# RiskChemi_Monitor_V1_05M1.net
KiCad netlist of a schematic drawn in Altium Designer
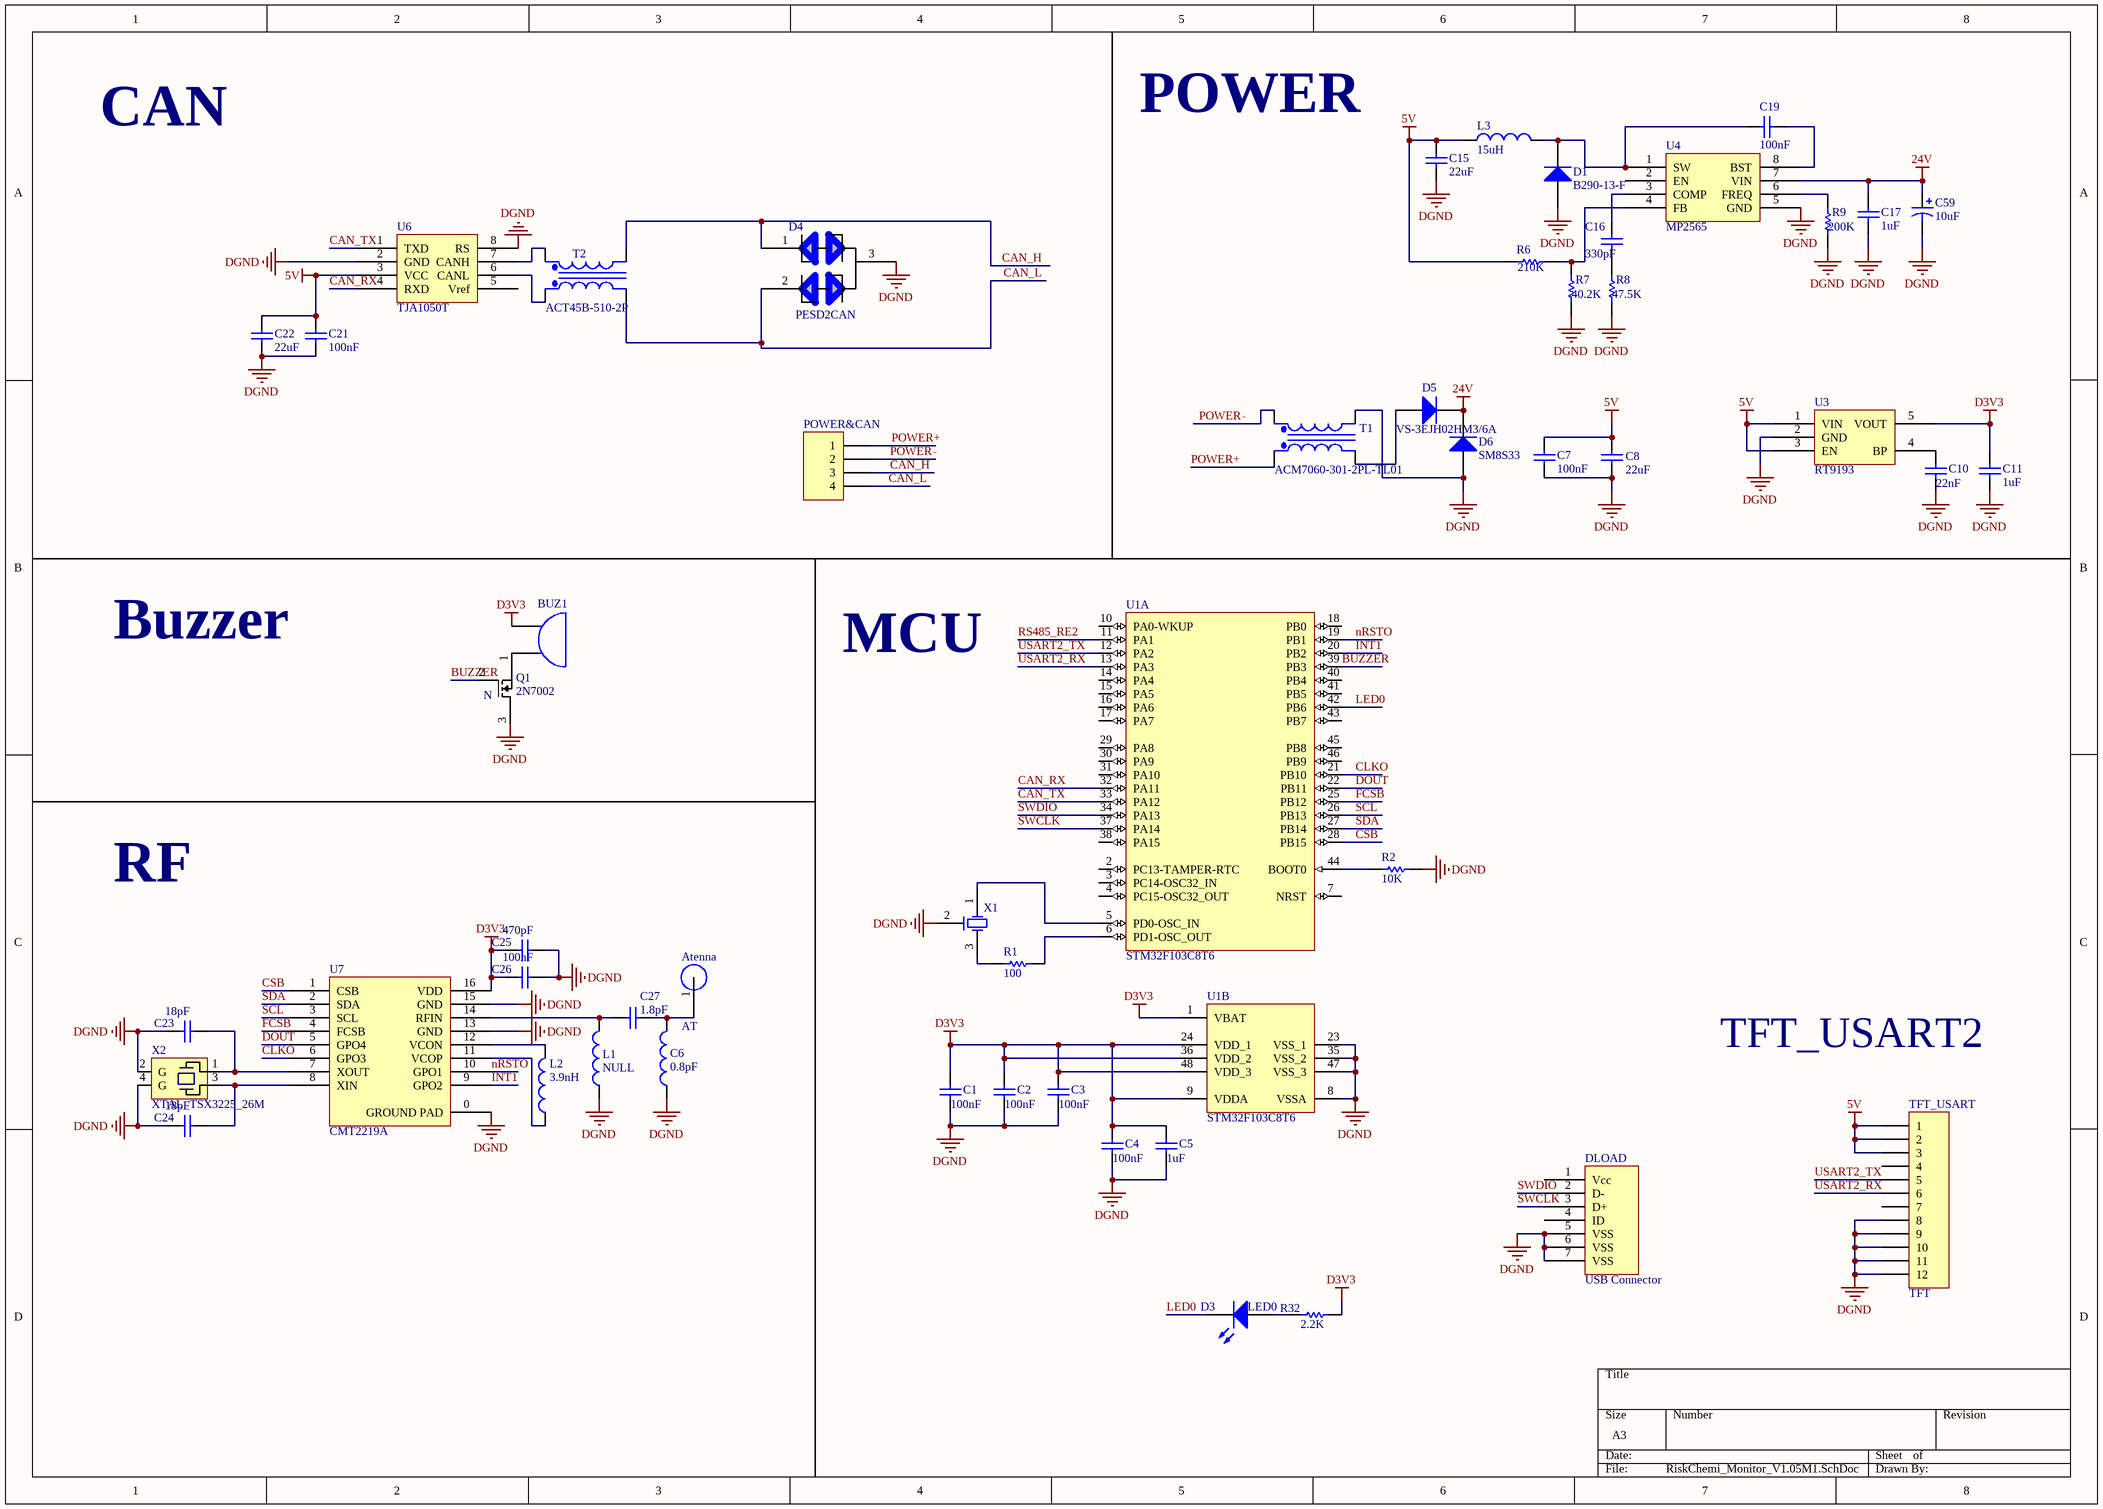
[diagram p0: RiskChemi_Monitor_V1.05M1.SchDoc]

(export (version "E")
  (design (tool "Eeschema 10.0.6"))
  (components
    (comp (ref "Atenna") (value "AT") (footprint "433MHz Atenna") (libsource (lib "MySchlib1") (part "AT")))
    (comp (ref "BUZ1")
      (value "BUZZER")
      (footprint "BUZ0905")
      (description "Buzzer")
      (libsource (lib "杂元件库") (part "BUZZER"))
    )
    (comp (ref "C1")
      (value "100nF")
      (footprint "0603")
      (description "Capacitor")
      (fields (field (name "PUBLISHER") "Altium Limited"))
      (libsource (lib "Miscellaneous Devices") (part "Cap"))
    )
    (comp (ref "C2")
      (value "100nF")
      (footprint "0603")
      (description "Capacitor")
      (fields (field (name "PUBLISHER") "Altium Limited"))
      (libsource (lib "Miscellaneous Devices") (part "Cap"))
    )
    (comp (ref "C3")
      (value "100nF")
      (footprint "0603")
      (description "Capacitor")
      (fields (field (name "PUBLISHER") "Altium Limited"))
      (libsource (lib "Miscellaneous Devices") (part "Cap"))
    )
    (comp (ref "C4")
      (value "100nF")
      (footprint "0603")
      (description "Capacitor")
      (fields (field (name "PUBLISHER") "Altium Limited"))
      (libsource (lib "Miscellaneous Devices") (part "Cap"))
    )
    (comp (ref "C5")
      (value "1uF")
      (footprint "0603")
      (description "Capacitor")
      (fields (field (name "PUBLISHER") "Altium Limited"))
      (libsource (lib "Miscellaneous Devices") (part "Cap"))
    )
    (comp (ref "C6")
      (value "0.8pF")
      (footprint "Miscellaneous Devices:0402")
      (description "Inductor")
      (fields (field (name "PUBLISHER") "Altium Limited"))
      (libsource (lib "Miscellaneous Devices") (part "Inductor"))
    )
    (comp (ref "C7")
      (value "100nF")
      (footprint "0805")
      (description "Capacitor,100V")
      (fields (field (name "PUBLISHER") "Altium Limited"))
      (libsource (lib "Miscellaneous Devices") (part "Cap"))
    )
    (comp (ref "C8")
      (value "22uF")
      (footprint "0805")
      (description "Capacitor")
      (fields (field (name "PUBLISHER") "Altium Limited"))
      (libsource (lib "Miscellaneous Devices") (part "Cap"))
    )
    (comp (ref "C10")
      (value "22nF")
      (footprint "BinFeng:0603")
      (description "Capacitor")
      (fields (field (name "PUBLISHER") "Altium Limited"))
      (libsource (lib "Miscellaneous Devices") (part "Cap"))
    )
    (comp (ref "C11")
      (value "1uF")
      (footprint "BinFeng:0603")
      (description "Capacitor")
      (fields (field (name "PUBLISHER") "Altium Limited"))
      (libsource (lib "Miscellaneous Devices") (part "Cap"))
    )
    (comp (ref "C15")
      (value "22uF")
      (footprint "0805")
      (description "Capacitor,50V")
      (fields (field (name "PUBLISHER") "Altium Limited"))
      (libsource (lib "Miscellaneous Devices") (part "Cap"))
    )
    (comp (ref "C16")
      (value "330pF")
      (footprint "BinFeng:0402")
      (description "Capacitor")
      (fields (field (name "PUBLISHER") "Altium Limited"))
      (libsource (lib "Miscellaneous Devices") (part "Cap"))
    )
    (comp (ref "C17")
      (value "1uF")
      (footprint "0805")
      (description "Capacitor,100V")
      (fields (field (name "PUBLISHER") "Altium Limited"))
      (libsource (lib "Miscellaneous Devices") (part "Cap"))
    )
    (comp (ref "C19")
      (value "100nF")
      (footprint "BinFeng:0402")
      (description "Capacitor")
      (fields (field (name "PUBLISHER") "Altium Limited"))
      (libsource (lib "Miscellaneous Devices") (part "Cap"))
    )
    (comp (ref "C21")
      (value "100nF")
      (footprint "0603")
      (description "Capacitor")
      (fields (field (name "PUBLISHER") "Altium Limited"))
      (libsource (lib "Miscellaneous Devices") (part "Cap"))
    )
    (comp (ref "C22")
      (value "22uF")
      (footprint "0805")
      (description "Capacitor")
      (fields (field (name "PUBLISHER") "Altium Limited"))
      (libsource (lib "Miscellaneous Devices") (part "Cap"))
    )
    (comp (ref "C23")
      (value "18pF")
      (footprint "BinFeng:0402")
      (description "Capacitor")
      (fields (field (name "PUBLISHER") "Altium Limited"))
      (libsource (lib "Miscellaneous Devices") (part "Cap"))
    )
    (comp (ref "C24")
      (value "18pF")
      (footprint "BinFeng:0402")
      (description "Capacitor")
      (fields (field (name "PUBLISHER") "Altium Limited"))
      (libsource (lib "Miscellaneous Devices") (part "Cap"))
    )
    (comp (ref "C25")
      (value "470pF")
      (footprint "BinFeng:0402")
      (description "Capacitor")
      (fields (field (name "PUBLISHER") "Altium Limited"))
      (libsource (lib "Miscellaneous Devices") (part "Cap"))
    )
    (comp (ref "C26")
      (value "100nF")
      (footprint "BinFeng:0603")
      (description "Capacitor")
      (fields (field (name "PUBLISHER") "Altium Limited"))
      (libsource (lib "Miscellaneous Devices") (part "Cap"))
    )
    (comp (ref "C27")
      (value "1.8pF")
      (footprint "BinFeng:nosilk_0402")
      (description "Capacitor")
      (fields (field (name "PUBLISHER") "Altium Limited"))
      (libsource (lib "Miscellaneous Devices") (part "Cap"))
    )
    (comp (ref "C59")
      (value "10uF")
      (footprint "6032_pol")
      (description "Polarized Capacitor (Radial)")
      (fields (field (name "PUBLISHER") "Altium Limited"))
      (libsource (lib "Miscellaneous Devices") (part "Cap Pol1"))
    )
    (comp (ref "D1")
      (value "B290-13-F")
      (footprint "back:B290")
      (description "Default Diode")
      (fields (field (name "PUBLISHER") "Altium Limited"))
      (libsource (lib "Miscellaneous Devices") (part "Diode"))
    )
    (comp (ref "D3")
      (value "LED0")
      (footprint "LED")
      (description "green LED")
      (fields (field (name "PUBLISHER") "Altium Limited"))
      (libsource (lib "Miscellaneous Devices") (part "LED0"))
    )
    (comp (ref "D4")
      (value "PESD2CAN")
      (footprint "SOT23")
      (libsource (lib "BinFeng_Connectors") (part "PESD1CAN"))
    )
    (comp (ref "D5")
      (value "VS-3EJH02HM3/6A")
      (footprint "back:B290")
      (description "1 Amp General Purpose Rectifier")
      (fields (field (name "PUBLISHER") "Altium Limited"))
      (libsource (lib "Miscellaneous Devices") (part "Diode 1N4007"))
    )
    (comp (ref "D6")
      (value "SM8S33")
      (footprint "SM8S")
      (description "1 Amp General Purpose Rectifier")
      (fields (field (name "PUBLISHER") "Altium Limited"))
      (libsource (lib "Miscellaneous Devices") (part "Diode 1N4007"))
    )
    (comp (ref "DLOAD")
      (value "USB Connector")
      (footprint "Mini_USB")
      (libsource (lib "BinFeng_Connectors") (part "Component_1"))
    )
    (comp (ref "L1")
      (value "NULL")
      (footprint "Miscellaneous Devices:0402")
      (description "Inductor")
      (fields (field (name "PUBLISHER") "Altium Limited"))
      (libsource (lib "Miscellaneous Devices") (part "Inductor"))
    )
    (comp (ref "L2")
      (value "3.9nH")
      (footprint "BinFeng:0603")
      (description "Inductor")
      (fields (field (name "PUBLISHER") "Altium Limited"))
      (libsource (lib "Miscellaneous Devices") (part "Inductor"))
    )
    (comp (ref "L3")
      (value "15uH")
      (footprint "4*4 Inductor")
      (description "Inductor, 1A")
      (fields (field (name "PUBLISHER") "Altium Limited"))
      (libsource (lib "Miscellaneous Devices") (part "Inductor"))
    )
    (comp (ref "POWER&CAN")
      (value "Header 4")
      (footprint "4_CLK_HEADER")
      (description "Header, 4-Pin")
      (fields (field (name "PUBLISHER") "Altium Limited"))
      (libsource (lib "Miscellaneous Connectors") (part "Header 4"))
    )
    (comp (ref "Q1") (value "2N7002") (footprint "2N7002") (libsource (lib "seeder") (part "N-MOSFET")))
    (comp (ref "R1")
      (value "100")
      (footprint "back:0603")
      (description "Resistor")
      (fields (field (name "PUBLISHER") "Altium Limited"))
      (libsource (lib "Miscellaneous Devices") (part "Res1"))
    )
    (comp (ref "R2")
      (value "10K")
      (footprint "back:0603")
      (description "Resistor")
      (fields (field (name "PUBLISHER") "Altium Limited"))
      (libsource (lib "Miscellaneous Devices") (part "Res1"))
    )
    (comp (ref "R6")
      (value "210K")
      (footprint "BinFeng:0402")
      (description "Resistor")
      (fields (field (name "PUBLISHER") "Altium Limited"))
      (libsource (lib "Miscellaneous Devices") (part "Res1"))
    )
    (comp (ref "R7")
      (value "40.2K")
      (footprint "BinFeng:0402")
      (description "Resistor")
      (fields (field (name "PUBLISHER") "Altium Limited"))
      (libsource (lib "Miscellaneous Devices") (part "Res1"))
    )
    (comp (ref "R8")
      (value "47.5K")
      (footprint "BinFeng:0402")
      (description "Resistor")
      (fields (field (name "PUBLISHER") "Altium Limited"))
      (libsource (lib "Miscellaneous Devices") (part "Res1"))
    )
    (comp (ref "R9")
      (value "200K")
      (footprint "BinFeng:0402")
      (description "Resistor")
      (fields (field (name "PUBLISHER") "Altium Limited"))
      (libsource (lib "Miscellaneous Devices") (part "Res1"))
    )
    (comp (ref "R32")
      (value "2.2K")
      (footprint "BinFeng:0603")
      (description "Resistor")
      (fields (field (name "PUBLISHER") "Altium Limited"))
      (libsource (lib "Miscellaneous Devices") (part "Res1"))
    )
    (comp (ref "T1")
      (value "ACM7060-301-2PL-TL01")
      (footprint "ACM7060-301-2P-TL01")
      (description "Transformer (Equivalent Circuit Model)")
      (fields (field (name "PUBLISHER") "Altium Limited"))
      (libsource (lib "Miscellaneous Devices") (part "Trans Eq"))
    )
    (comp (ref "T2")
      (value "ACT45B-510-2P")
      (footprint "ACT45B-510-2P")
      (description "Transformer (Equivalent Circuit Model)")
      (fields (field (name "PUBLISHER") "Altium Limited"))
      (libsource (lib "Miscellaneous Devices") (part "Trans Eq"))
    )
    (comp (ref "TFT_USART")
      (value "TFT")
      (footprint "FCC_10pin_1mm")
      (description "Header, 12-Pin")
      (fields (field (name "PUBLISHER") "Altium Limited"))
      (libsource (lib "Miscellaneous Connectors") (part "Header 12"))
    )
    (comp (ref "U1")
      (value "STM32F103C8T6")
      (footprint "STM-LQFP48_N")
      (libsource (lib "STMicroelectronics STM32 F1") (part "STM32F103C8T6"))
    )
    (comp (ref "U3") (value "RT9193") (footprint "SOT-23-5") (libsource (lib "BinFeng_IC") (part "RT9193")))
    (comp (ref "U4")
      (value "MP2565")
      (footprint "SO8")
      (description "DCDC 4.5V~28V input 1.8V ~5V output low power")
      (libsource (lib "BinFeng_IC") (part "MP1584"))
    )
    (comp (ref "U6")
      (value "TJA1050T")
      (footprint "SO8")
      (description "CAN Tranceiver")
      (libsource (lib "BinFeng_IC") (part "TJA1050T"))
    )
    (comp (ref "U7")
      (value "CMT2219A")
      (footprint "back:QFN16")
      (libsource (lib "BinFeng_IC") (part "CMT2219A"))
    )
    (comp (ref "X1") (value "8M smd") (footprint "8Mhz_XTAL") (libsource (lib "Schlib1") (part "8M smd")))
    (comp (ref "X2")
      (value "XTAL_TSX3225_26M")
      (footprint "XTAL3225")
      (libsource (lib "BinFeng_IC") (part "XTAL_Negative"))
    )
  )
  (nets
    (net (code "1") (name "/BUZZER") (class "Default")
      (node (ref "Q1") (pin "2") (pinfunction "G_2") (pintype "passive"))
      (node (ref "U1") (pin "39") (pinfunction "PB3_39") (pintype "bidirectional"))
    )
    (net (code "2") (name "/CAN_H") (class "Default")
      (node (ref "D4") (pin "1") (pinfunction "11_1") (pintype "passive"))
      (node (ref "POWER&CAN") (pin "3") (pinfunction "3_3") (pintype "passive"))
      (node (ref "T2") (pin "4") (pinfunction "Sec-_4") (pintype "passive"))
    )
    (net (code "3") (name "/CAN_L") (class "Default")
      (node (ref "D4") (pin "2") (pinfunction "12_2") (pintype "passive"))
      (node (ref "POWER&CAN") (pin "4") (pinfunction "4_4") (pintype "passive"))
      (node (ref "T2") (pin "2") (pinfunction "Pri-_2") (pintype "passive"))
    )
    (net (code "4") (name "/CAN_RX") (class "Default")
      (node (ref "U1") (pin "32") (pinfunction "PA11_32") (pintype "bidirectional"))
      (node (ref "U6") (pin "4") (pinfunction "RXD_4") (pintype "passive"))
    )
    (net (code "5") (name "/CAN_TX") (class "Default")
      (node (ref "U1") (pin "33") (pinfunction "PA12_33") (pintype "bidirectional"))
      (node (ref "U6") (pin "1") (pinfunction "TXD_1") (pintype "passive"))
    )
    (net (code "6") (name "/CLKO") (class "Default")
      (node (ref "U1") (pin "21") (pinfunction "PB10_21") (pintype "bidirectional"))
      (node (ref "U7") (pin "6") (pinfunction "GPO3_6") (pintype "passive"))
    )
    (net (code "7") (name "/CSB") (class "Default")
      (node (ref "U1") (pin "28") (pinfunction "PB15_28") (pintype "bidirectional"))
      (node (ref "U7") (pin "1") (pinfunction "CSB_1") (pintype "passive"))
    )
    (net (code "8") (name "/DOUT") (class "Default")
      (node (ref "U1") (pin "22") (pinfunction "PB11_22") (pintype "bidirectional"))
      (node (ref "U7") (pin "5") (pinfunction "GPO4_5") (pintype "passive"))
    )
    (net (code "9") (name "/FCSB") (class "Default")
      (node (ref "U1") (pin "25") (pinfunction "PB12_25") (pintype "bidirectional"))
      (node (ref "U7") (pin "4") (pinfunction "FCSB_4") (pintype "passive"))
    )
    (net (code "10") (name "/INT1") (class "Default")
      (node (ref "U1") (pin "20") (pinfunction "PB2_20") (pintype "bidirectional"))
      (node (ref "U7") (pin "9") (pinfunction "GPO2_9") (pintype "passive"))
    )
    (net (code "11") (name "/LED0") (class "Default")
      (node (ref "D3") (pin "2") (pinfunction "K_2") (pintype "passive"))
      (node (ref "U1") (pin "42") (pinfunction "PB6_42") (pintype "bidirectional"))
    )
    (net (code "12") (name "/POWER+") (class "Default")
      (node (ref "POWER&CAN") (pin "1") (pinfunction "1_1") (pintype "passive"))
      (node (ref "T1") (pin "1") (pinfunction "Pri+_1") (pintype "passive"))
    )
    (net (code "13") (name "/POWER﹣") (class "Default")
      (node (ref "POWER&CAN") (pin "2") (pinfunction "2_2") (pintype "passive"))
      (node (ref "T1") (pin "3") (pinfunction "Sec+_3") (pintype "passive"))
    )
    (net (code "14") (name "/RS485_RE2") (class "Default")
      (node (ref "U1") (pin "11") (pinfunction "PA1_11") (pintype "bidirectional"))
    )
    (net (code "15") (name "/SCL") (class "Default")
      (node (ref "U1") (pin "26") (pinfunction "PB13_26") (pintype "bidirectional"))
      (node (ref "U7") (pin "3") (pinfunction "SCL_3") (pintype "passive"))
    )
    (net (code "16") (name "/SDA") (class "Default")
      (node (ref "U1") (pin "27") (pinfunction "PB14_27") (pintype "bidirectional"))
      (node (ref "U7") (pin "2") (pinfunction "SDA_2") (pintype "passive"))
    )
    (net (code "17") (name "/SWCLK") (class "Default")
      (node (ref "DLOAD") (pin "3") (pinfunction "D+_3") (pintype "passive"))
      (node (ref "U1") (pin "37") (pinfunction "PA14_37") (pintype "bidirectional"))
    )
    (net (code "18") (name "/SWDIO") (class "Default")
      (node (ref "DLOAD") (pin "2") (pinfunction "D-_2") (pintype "passive"))
      (node (ref "U1") (pin "34") (pinfunction "PA13_34") (pintype "bidirectional"))
    )
    (net (code "19") (name "/USART2_RX") (class "Default")
      (node (ref "TFT_USART") (pin "6") (pinfunction "6_6") (pintype "passive"))
      (node (ref "U1") (pin "13") (pinfunction "PA3_13") (pintype "bidirectional"))
    )
    (net (code "20") (name "/USART2_TX") (class "Default")
      (node (ref "TFT_USART") (pin "5") (pinfunction "5_5") (pintype "passive"))
      (node (ref "U1") (pin "12") (pinfunction "PA2_12") (pintype "bidirectional"))
    )
    (net (code "21") (name "/nRSTO") (class "Default")
      (node (ref "U1") (pin "19") (pinfunction "PB1_19") (pintype "bidirectional"))
      (node (ref "U7") (pin "10") (pinfunction "GPO1_10") (pintype "passive"))
    )
    (net (code "22") (name "5V") (class "Default")
      (node (ref "C15") (pin "2") (pinfunction "2_2") (pintype "passive"))
      (node (ref "C21") (pin "1") (pinfunction "1_1") (pintype "passive"))
      (node (ref "C22") (pin "2") (pinfunction "2_2") (pintype "passive"))
      (node (ref "C7") (pin "2") (pinfunction "2_2") (pintype "passive"))
      (node (ref "C8") (pin "2") (pinfunction "2_2") (pintype "passive"))
      (node (ref "L3") (pin "1") (pinfunction "1_1") (pintype "passive"))
      (node (ref "R6") (pin "2") (pinfunction "2_2") (pintype "passive"))
      (node (ref "TFT_USART") (pin "1") (pinfunction "1_1") (pintype "passive"))
      (node (ref "TFT_USART") (pin "2") (pinfunction "2_2") (pintype "passive"))
      (node (ref "TFT_USART") (pin "3") (pinfunction "3_3") (pintype "passive"))
      (node (ref "U3") (pin "1") (pinfunction "VIN_1") (pintype "passive"))
      (node (ref "U3") (pin "3") (pinfunction "EN_3") (pintype "passive"))
      (node (ref "U6") (pin "3") (pinfunction "VCC_3") (pintype "passive"))
    )
    (net (code "23") (name "24V") (class "Default")
      (node (ref "C17") (pin "2") (pinfunction "2_2") (pintype "passive"))
      (node (ref "C59") (pin "1") (pinfunction "1_1") (pintype "passive"))
      (node (ref "D5") (pin "2") (pinfunction "K_2") (pintype "passive"))
      (node (ref "D6") (pin "2") (pinfunction "K_2") (pintype "passive"))
      (node (ref "U4") (pin "7") (pinfunction "VIN_7") (pintype "passive"))
    )
    (net (code "24") (name "D3V3") (class "Default")
      (node (ref "BUZ1") (pin "1") (pinfunction "A_1") (pintype "passive"))
      (node (ref "C1") (pin "2") (pinfunction "2_2") (pintype "passive"))
      (node (ref "C11") (pin "2") (pinfunction "2_2") (pintype "passive"))
      (node (ref "C2") (pin "2") (pinfunction "2_2") (pintype "passive"))
      (node (ref "C25") (pin "2") (pinfunction "2_2") (pintype "passive"))
      (node (ref "C26") (pin "2") (pinfunction "2_2") (pintype "passive"))
      (node (ref "C3") (pin "2") (pinfunction "2_2") (pintype "passive"))
      (node (ref "C4") (pin "2") (pinfunction "2_2") (pintype "passive"))
      (node (ref "C5") (pin "2") (pinfunction "2_2") (pintype "passive"))
      (node (ref "R32") (pin "1") (pinfunction "1_1") (pintype "passive"))
      (node (ref "U1") (pin "1") (pinfunction "VBAT_1") (pintype "power_in"))
      (node (ref "U1") (pin "24") (pinfunction "VDD_1_24") (pintype "power_in"))
      (node (ref "U1") (pin "36") (pinfunction "VDD_2_36") (pintype "power_in"))
      (node (ref "U1") (pin "48") (pinfunction "VDD_3_48") (pintype "power_in"))
      (node (ref "U1") (pin "9") (pinfunction "VDDA_9") (pintype "power_in"))
      (node (ref "U3") (pin "5") (pinfunction "VOUT_5") (pintype "passive"))
      (node (ref "U7") (pin "16") (pinfunction "VDD_16") (pintype "passive"))
    )
    (net (code "25") (name "DGND") (class "Default")
      (node (ref "C1") (pin "1") (pinfunction "1_1") (pintype "passive"))
      (node (ref "C10") (pin "1") (pinfunction "1_1") (pintype "passive"))
      (node (ref "C11") (pin "1") (pinfunction "1_1") (pintype "passive"))
      (node (ref "C15") (pin "1") (pinfunction "1_1") (pintype "passive"))
      (node (ref "C17") (pin "1") (pinfunction "1_1") (pintype "passive"))
      (node (ref "C2") (pin "1") (pinfunction "1_1") (pintype "passive"))
      (node (ref "C21") (pin "2") (pinfunction "2_2") (pintype "passive"))
      (node (ref "C22") (pin "1") (pinfunction "1_1") (pintype "passive"))
      (node (ref "C23") (pin "2") (pinfunction "2_2") (pintype "passive"))
      (node (ref "C24") (pin "2") (pinfunction "2_2") (pintype "passive"))
      (node (ref "C25") (pin "1") (pinfunction "1_1") (pintype "passive"))
      (node (ref "C26") (pin "1") (pinfunction "1_1") (pintype "passive"))
      (node (ref "C3") (pin "1") (pinfunction "1_1") (pintype "passive"))
      (node (ref "C4") (pin "1") (pinfunction "1_1") (pintype "passive"))
      (node (ref "C5") (pin "1") (pinfunction "1_1") (pintype "passive"))
      (node (ref "C59") (pin "2") (pinfunction "2_2") (pintype "passive"))
      (node (ref "C6") (pin "1") (pinfunction "1_1") (pintype "passive"))
      (node (ref "C7") (pin "1") (pinfunction "1_1") (pintype "passive"))
      (node (ref "C8") (pin "1") (pinfunction "1_1") (pintype "passive"))
      (node (ref "D1") (pin "1") (pinfunction "A_1") (pintype "passive"))
      (node (ref "D4") (pin "3") (pinfunction "13_3") (pintype "passive"))
      (node (ref "D6") (pin "1") (pinfunction "A_1") (pintype "passive"))
      (node (ref "DLOAD") (pin "5") (pinfunction "VSS_5") (pintype "passive"))
      (node (ref "DLOAD") (pin "6") (pinfunction "VSS_6") (pintype "passive"))
      (node (ref "DLOAD") (pin "7") (pinfunction "VSS_7") (pintype "passive"))
      (node (ref "L1") (pin "1") (pinfunction "1_1") (pintype "passive"))
      (node (ref "Q1") (pin "3") (pinfunction "S_3") (pintype "passive"))
      (node (ref "R2") (pin "2") (pinfunction "2_2") (pintype "passive"))
      (node (ref "R7") (pin "1") (pinfunction "1_1") (pintype "passive"))
      (node (ref "R8") (pin "1") (pinfunction "1_1") (pintype "passive"))
      (node (ref "R9") (pin "1") (pinfunction "1_1") (pintype "passive"))
      (node (ref "T1") (pin "4") (pinfunction "Sec-_4") (pintype "passive"))
      (node (ref "TFT_USART") (pin "10") (pinfunction "10_10") (pintype "passive"))
      (node (ref "TFT_USART") (pin "11") (pinfunction "11_11") (pintype "passive"))
      (node (ref "TFT_USART") (pin "12") (pinfunction "12_12") (pintype "passive"))
      (node (ref "TFT_USART") (pin "8") (pinfunction "8_8") (pintype "passive"))
      (node (ref "TFT_USART") (pin "9") (pinfunction "9_9") (pintype "passive"))
      (node (ref "U1") (pin "23") (pinfunction "VSS_1_23") (pintype "power_in"))
      (node (ref "U1") (pin "35") (pinfunction "VSS_2_35") (pintype "power_in"))
      (node (ref "U1") (pin "47") (pinfunction "VSS_3_47") (pintype "power_in"))
      (node (ref "U1") (pin "8") (pinfunction "VSSA_8") (pintype "power_in"))
      (node (ref "U3") (pin "2") (pinfunction "GND_2") (pintype "passive"))
      (node (ref "U4") (pin "5") (pinfunction "GND_5") (pintype "passive"))
      (node (ref "U6") (pin "2") (pinfunction "GND_2") (pintype "passive"))
      (node (ref "U6") (pin "8") (pinfunction "RS_8") (pintype "passive"))
      (node (ref "U7") (pin "0") (pinfunction "GROUND_PAD_0") (pintype "passive"))
      (node (ref "U7") (pin "13") (pinfunction "GND_13") (pintype "passive"))
      (node (ref "U7") (pin "15") (pinfunction "GND_15") (pintype "passive"))
      (node (ref "X1") (pin "2") (pinfunction "GND_2") (pintype "passive"))
      (node (ref "X2") (pin "2") (pinfunction "G_2") (pintype "passive"))
      (node (ref "X2") (pin "4") (pinfunction "G_4") (pintype "passive"))
    )
    (net (code "26") (name "Net-(Atenna-Pad1)") (class "Default")
      (node (ref "Atenna") (pin "1") (pinfunction "1_1") (pintype "passive"))
      (node (ref "C27") (pin "1") (pinfunction "1_1") (pintype "passive"))
      (node (ref "C6") (pin "2") (pinfunction "2_2") (pintype "passive"))
    )
    (net (code "27") (name "Net-(BUZ1-B)") (class "Default")
      (node (ref "BUZ1") (pin "2") (pinfunction "B_2") (pintype "passive"))
      (node (ref "Q1") (pin "1") (pinfunction "D_1") (pintype "passive"))
    )
    (net (code "28") (name "Net-(C16-Pad2)") (class "Default")
      (node (ref "C16") (pin "2") (pinfunction "2_2") (pintype "passive"))
      (node (ref "R8") (pin "2") (pinfunction "2_2") (pintype "passive"))
    )
    (net (code "29") (name "Net-(D1-K)") (class "Default")
      (node (ref "C19") (pin "2") (pinfunction "2_2") (pintype "passive"))
      (node (ref "D1") (pin "2") (pinfunction "K_2") (pintype "passive"))
      (node (ref "L3") (pin "2") (pinfunction "2_2") (pintype "passive"))
      (node (ref "U4") (pin "1") (pinfunction "SW_1") (pintype "passive"))
    )
    (net (code "30") (name "Net-(D3-A)") (class "Default")
      (node (ref "D3") (pin "1") (pinfunction "A_1") (pintype "passive"))
      (node (ref "R32") (pin "2") (pinfunction "2_2") (pintype "passive"))
    )
    (net (code "31") (name "Net-(D5-A)") (class "Default")
      (node (ref "D5") (pin "1") (pinfunction "A_1") (pintype "passive"))
      (node (ref "T1") (pin "2") (pinfunction "Pri-_2") (pintype "passive"))
    )
    (net (code "32") (name "Net-(T2-Pri+)") (class "Default")
      (node (ref "T2") (pin "1") (pinfunction "Pri+_1") (pintype "passive"))
      (node (ref "U6") (pin "6") (pinfunction "CANL_6") (pintype "passive"))
    )
    (net (code "33") (name "Net-(T2-Sec+)") (class "Default")
      (node (ref "T2") (pin "3") (pinfunction "Sec+_3") (pintype "passive"))
      (node (ref "U6") (pin "7") (pinfunction "CANH_7") (pintype "passive"))
    )
    (net (code "34") (name "Net-(U1A-BOOT0)") (class "Default")
      (node (ref "R2") (pin "1") (pinfunction "1_1") (pintype "passive"))
      (node (ref "U1") (pin "44") (pinfunction "BOOT0_44") (pintype "input"))
    )
    (net (code "35") (name "Net-(U1A-PD0-OSC_IN)") (class "Default")
      (node (ref "U1") (pin "5") (pinfunction "PD0-OSC_IN_5") (pintype "bidirectional"))
      (node (ref "X1") (pin "1") (pinfunction "OSC1_1") (pintype "passive"))
    )
    (net (code "36") (name "Net-(U1A-PD1-OSC_OUT)") (class "Default")
      (node (ref "R1") (pin "2") (pinfunction "2_2") (pintype "passive"))
      (node (ref "U1") (pin "6") (pinfunction "PD1-OSC_OUT_6") (pintype "bidirectional"))
    )
    (net (code "37") (name "Net-(U3-BP)") (class "Default")
      (node (ref "C10") (pin "2") (pinfunction "2_2") (pintype "passive"))
      (node (ref "U3") (pin "4") (pinfunction "BP_4") (pintype "passive"))
    )
    (net (code "38") (name "Net-(U4-BST)") (class "Default")
      (node (ref "C19") (pin "1") (pinfunction "1_1") (pintype "passive"))
      (node (ref "U4") (pin "8") (pinfunction "BST_8") (pintype "passive"))
    )
    (net (code "39") (name "Net-(U4-COMP)") (class "Default")
      (node (ref "C16") (pin "1") (pinfunction "1_1") (pintype "passive"))
      (node (ref "U4") (pin "3") (pinfunction "COMP_3") (pintype "passive"))
    )
    (net (code "40") (name "Net-(U4-FB)") (class "Default")
      (node (ref "R6") (pin "1") (pinfunction "1_1") (pintype "passive"))
      (node (ref "R7") (pin "2") (pinfunction "2_2") (pintype "passive"))
      (node (ref "U4") (pin "4") (pinfunction "FB_4") (pintype "passive"))
    )
    (net (code "41") (name "Net-(U4-FREQ)") (class "Default")
      (node (ref "R9") (pin "2") (pinfunction "2_2") (pintype "passive"))
      (node (ref "U4") (pin "6") (pinfunction "FREQ_6") (pintype "passive"))
    )
    (net (code "42") (name "Net-(U7-RFIN)") (class "Default")
      (node (ref "C27") (pin "2") (pinfunction "2_2") (pintype "passive"))
      (node (ref "L1") (pin "2") (pinfunction "2_2") (pintype "passive"))
      (node (ref "U7") (pin "14") (pinfunction "RFIN_14") (pintype "passive"))
    )
    (net (code "43") (name "Net-(U7-VCON)") (class "Default")
      (node (ref "L2") (pin "2") (pinfunction "2_2") (pintype "passive"))
      (node (ref "U7") (pin "12") (pinfunction "VCON_12") (pintype "passive"))
    )
    (net (code "44") (name "Net-(U7-VCOP)") (class "Default")
      (node (ref "L2") (pin "1") (pinfunction "1_1") (pintype "passive"))
      (node (ref "U7") (pin "11") (pinfunction "VCOP_11") (pintype "passive"))
    )
    (net (code "45") (name "Net-(U7-XIN)") (class "Default")
      (node (ref "C24") (pin "1") (pinfunction "1_1") (pintype "passive"))
      (node (ref "U7") (pin "8") (pinfunction "XIN_8") (pintype "passive"))
      (node (ref "X2") (pin "3") (pintype "passive"))
    )
    (net (code "46") (name "Net-(U7-XOUT)") (class "Default")
      (node (ref "C23") (pin "1") (pinfunction "1_1") (pintype "passive"))
      (node (ref "U7") (pin "7") (pinfunction "XOUT_7") (pintype "passive"))
      (node (ref "X2") (pin "1") (pintype "passive"))
    )
    (net (code "47") (name "Net-(X1-OSC2)") (class "Default")
      (node (ref "R1") (pin "1") (pinfunction "1_1") (pintype "passive"))
      (node (ref "X1") (pin "3") (pinfunction "OSC2_3") (pintype "passive"))
    )
    (net (code "48") (name "unconnected-(DLOAD-ID-Pad4)") (class "Default")
      (node (ref "DLOAD") (pin "4") (pinfunction "ID_4") (pintype "passive"))
    )
    (net (code "49") (name "unconnected-(DLOAD-Vcc-Pad1)") (class "Default")
      (node (ref "DLOAD") (pin "1") (pinfunction "Vcc_1") (pintype "passive"))
    )
    (net (code "50") (name "unconnected-(TFT_USART-Pad4)") (class "Default")
      (node (ref "TFT_USART") (pin "4") (pinfunction "4_4") (pintype "passive"))
    )
    (net (code "51") (name "unconnected-(TFT_USART-Pad7)") (class "Default")
      (node (ref "TFT_USART") (pin "7") (pinfunction "7_7") (pintype "passive"))
    )
    (net (code "52") (name "unconnected-(U1A-NRST-Pad7)") (class "Default")
      (node (ref "U1") (pin "7") (pinfunction "NRST_7") (pintype "bidirectional"))
    )
    (net (code "53") (name "unconnected-(U1A-PA0-WKUP-Pad10)") (class "Default")
      (node (ref "U1") (pin "10") (pinfunction "PA0-WKUP_10") (pintype "bidirectional"))
    )
    (net (code "54") (name "unconnected-(U1A-PA4-Pad14)") (class "Default")
      (node (ref "U1") (pin "14") (pinfunction "PA4_14") (pintype "bidirectional"))
    )
    (net (code "55") (name "unconnected-(U1A-PA5-Pad15)") (class "Default")
      (node (ref "U1") (pin "15") (pinfunction "PA5_15") (pintype "bidirectional"))
    )
    (net (code "56") (name "unconnected-(U1A-PA6-Pad16)") (class "Default")
      (node (ref "U1") (pin "16") (pinfunction "PA6_16") (pintype "bidirectional"))
    )
    (net (code "57") (name "unconnected-(U1A-PA7-Pad17)") (class "Default")
      (node (ref "U1") (pin "17") (pinfunction "PA7_17") (pintype "bidirectional"))
    )
    (net (code "58") (name "unconnected-(U1A-PA8-Pad29)") (class "Default")
      (node (ref "U1") (pin "29") (pinfunction "PA8_29") (pintype "bidirectional"))
    )
    (net (code "59") (name "unconnected-(U1A-PA9-Pad30)") (class "Default")
      (node (ref "U1") (pin "30") (pinfunction "PA9_30") (pintype "bidirectional"))
    )
    (net (code "60") (name "unconnected-(U1A-PA10-Pad31)") (class "Default")
      (node (ref "U1") (pin "31") (pinfunction "PA10_31") (pintype "bidirectional"))
    )
    (net (code "61") (name "unconnected-(U1A-PA15-Pad38)") (class "Default")
      (node (ref "U1") (pin "38") (pinfunction "PA15_38") (pintype "bidirectional"))
    )
    (net (code "62") (name "unconnected-(U1A-PB0-Pad18)") (class "Default")
      (node (ref "U1") (pin "18") (pinfunction "PB0_18") (pintype "bidirectional"))
    )
    (net (code "63") (name "unconnected-(U1A-PB4-Pad40)") (class "Default")
      (node (ref "U1") (pin "40") (pinfunction "PB4_40") (pintype "bidirectional"))
    )
    (net (code "64") (name "unconnected-(U1A-PB5-Pad41)") (class "Default")
      (node (ref "U1") (pin "41") (pinfunction "PB5_41") (pintype "bidirectional"))
    )
    (net (code "65") (name "unconnected-(U1A-PB7-Pad43)") (class "Default")
      (node (ref "U1") (pin "43") (pinfunction "PB7_43") (pintype "bidirectional"))
    )
    (net (code "66") (name "unconnected-(U1A-PB8-Pad45)") (class "Default")
      (node (ref "U1") (pin "45") (pinfunction "PB8_45") (pintype "bidirectional"))
    )
    (net (code "67") (name "unconnected-(U1A-PB9-Pad46)") (class "Default")
      (node (ref "U1") (pin "46") (pinfunction "PB9_46") (pintype "bidirectional"))
    )
    (net (code "68") (name "unconnected-(U1A-PC13-TAMPER-RTC-Pad2)") (class "Default")
      (node (ref "U1") (pin "2") (pinfunction "PC13-TAMPER-RTC_2") (pintype "bidirectional"))
    )
    (net (code "69") (name "unconnected-(U1A-PC14-OSC32_IN-Pad3)") (class "Default")
      (node (ref "U1") (pin "3") (pinfunction "PC14-OSC32_IN_3") (pintype "bidirectional"))
    )
    (net (code "70") (name "unconnected-(U1A-PC15-OSC32_OUT-Pad4)") (class "Default")
      (node (ref "U1") (pin "4") (pinfunction "PC15-OSC32_OUT_4") (pintype "bidirectional"))
    )
    (net (code "71") (name "unconnected-(U4-EN-Pad2)") (class "Default")
      (node (ref "U4") (pin "2") (pinfunction "EN_2") (pintype "passive"))
    )
    (net (code "72") (name "unconnected-(U6-Vref-Pad5)") (class "Default")
      (node (ref "U6") (pin "5") (pinfunction "Vref_5") (pintype "passive"))
    )
  )
)
